# EspSwitchNode.net
KiCad netlist of a schematic drawn in EAGLE
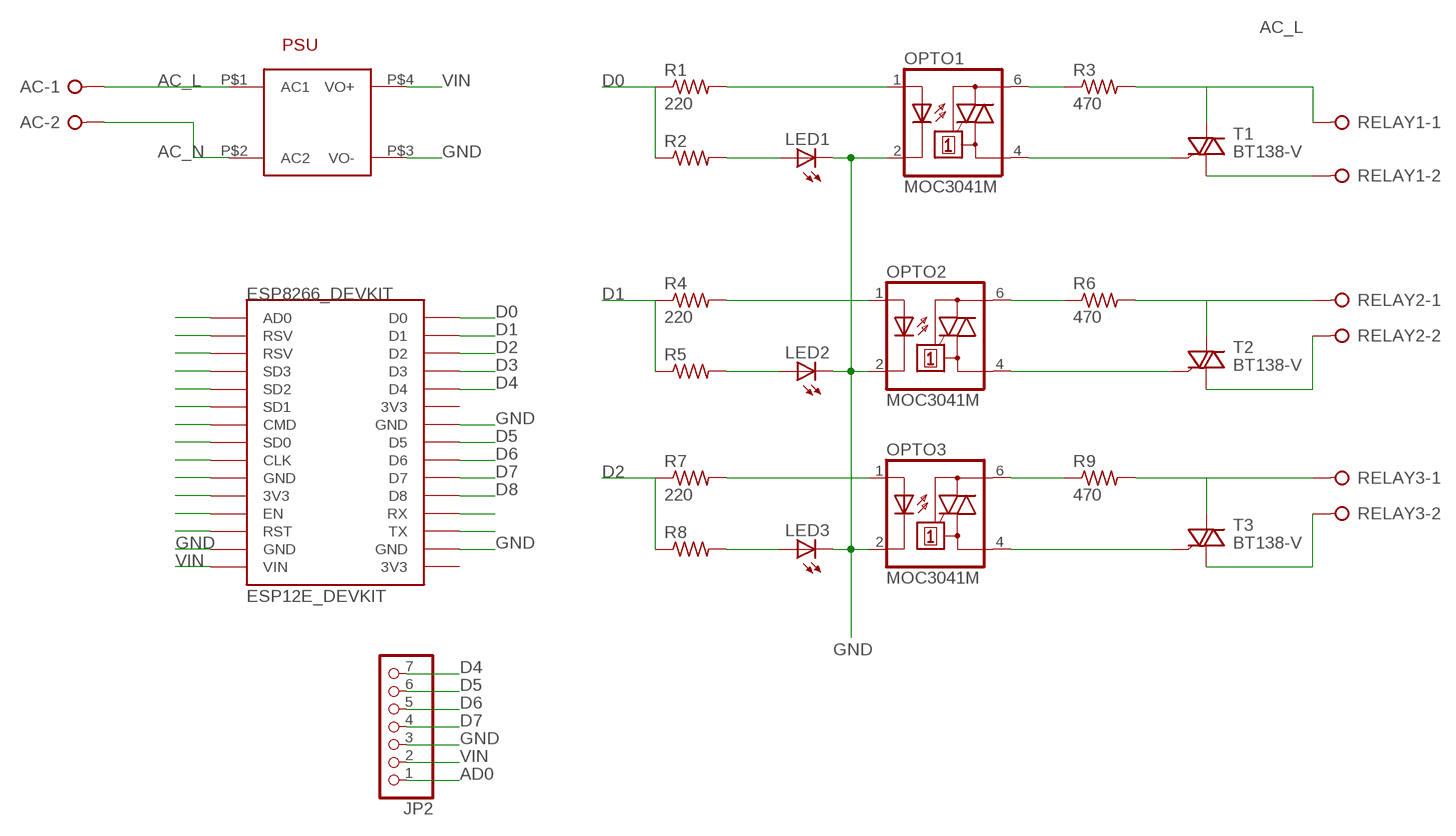
[diagram p0: schematic, sheet 1]

(export (version "E")
  (design (tool "Eeschema 10.0.6"))
  (components
    (comp (ref "AC")
      (value "W237-02P")
      (footprint "eagle-import:W237-132")
      (libsource (lib "eagle-import") (part "W237-02P"))
    )
    (comp (ref "ESP8266_DEVKIT")
      (value "ESP12E_DEVKIT")
      (footprint "eagle-import:ESP12E_DEVKIT")
      (libsource (lib "eagle-import") (part "ESP12E_DEVKIT"))
    )
    (comp (ref "JP2")
      (value "PINHD-1X7")
      (footprint "eagle-import:1X07")
      (libsource (lib "eagle-import") (part "PINHD-1X7"))
    )
    (comp (ref "LED1")
      (value "LEDCHIPLED_0805")
      (footprint "eagle-import:CHIPLED_0805")
      (libsource (lib "eagle-import") (part "LEDCHIPLED_0805"))
    )
    (comp (ref "LED2")
      (value "LEDCHIPLED_0805")
      (footprint "eagle-import:CHIPLED_0805")
      (libsource (lib "eagle-import") (part "LEDCHIPLED_0805"))
    )
    (comp (ref "LED3")
      (value "LEDCHIPLED_0805")
      (footprint "eagle-import:CHIPLED_0805")
      (libsource (lib "eagle-import") (part "LEDCHIPLED_0805"))
    )
    (comp (ref "OPTO1")
      (value "MOC3041M")
      (footprint "eagle-import:DIL06")
      (fields (field (name "MF") "FAIRCHILD SEMICONDUCTOR"))
      (libsource (lib "eagle-import") (part "MOC3041M"))
    )
    (comp (ref "OPTO2")
      (value "MOC3041M")
      (footprint "eagle-import:DIL06")
      (fields (field (name "MF") "FAIRCHILD SEMICONDUCTOR"))
      (libsource (lib "eagle-import") (part "MOC3041M"))
    )
    (comp (ref "OPTO3")
      (value "MOC3041M")
      (footprint "eagle-import:DIL06")
      (fields (field (name "MF") "FAIRCHILD SEMICONDUCTOR"))
      (libsource (lib "eagle-import") (part "MOC3041M"))
    )
    (comp (ref "PSU")
      (value "HLK-PM01")
      (footprint "eagle-import:HLK-PM01")
      (libsource (lib "eagle-import") (part "HLK-PM01"))
    )
    (comp (ref "R1")
      (value "220")
      (footprint "eagle-import:M0805")
      (libsource (lib "eagle-import") (part "R-US_M0805"))
    )
    (comp (ref "R2")
      (value "R-US_M0805")
      (footprint "eagle-import:M0805")
      (libsource (lib "eagle-import") (part "R-US_M0805"))
    )
    (comp (ref "R3")
      (value "470")
      (footprint "eagle-import:M0805")
      (libsource (lib "eagle-import") (part "R-US_M0805"))
    )
    (comp (ref "R4")
      (value "220")
      (footprint "eagle-import:M0805")
      (libsource (lib "eagle-import") (part "R-US_M0805"))
    )
    (comp (ref "R5")
      (value "R-US_M0805")
      (footprint "eagle-import:M0805")
      (libsource (lib "eagle-import") (part "R-US_M0805"))
    )
    (comp (ref "R6")
      (value "470")
      (footprint "eagle-import:M0805")
      (libsource (lib "eagle-import") (part "R-US_M0805"))
    )
    (comp (ref "R7")
      (value "220")
      (footprint "eagle-import:M0805")
      (libsource (lib "eagle-import") (part "R-US_M0805"))
    )
    (comp (ref "R8")
      (value "R-US_M0805")
      (footprint "eagle-import:M0805")
      (libsource (lib "eagle-import") (part "R-US_M0805"))
    )
    (comp (ref "R9")
      (value "470")
      (footprint "eagle-import:M0805")
      (libsource (lib "eagle-import") (part "R-US_M0805"))
    )
    (comp (ref "RELAY1")
      (value "W237-02P")
      (footprint "eagle-import:W237-132")
      (libsource (lib "eagle-import") (part "W237-02P"))
    )
    (comp (ref "RELAY2")
      (value "W237-02P")
      (footprint "eagle-import:W237-132")
      (libsource (lib "eagle-import") (part "W237-02P"))
    )
    (comp (ref "RELAY3")
      (value "W237-02P")
      (footprint "eagle-import:W237-132")
      (libsource (lib "eagle-import") (part "W237-02P"))
    )
    (comp (ref "T1")
      (value "BT138-V")
      (footprint "eagle-import:TO220BV")
      (libsource (lib "eagle-import") (part "BT138-V"))
    )
    (comp (ref "T2")
      (value "BT138-V")
      (footprint "eagle-import:TO220BV")
      (libsource (lib "eagle-import") (part "BT138-V"))
    )
    (comp (ref "T3")
      (value "BT138-V")
      (footprint "eagle-import:TO220BV")
      (libsource (lib "eagle-import") (part "BT138-V"))
    )
  )
  (nets
    (net (code "1") (name "/AC_L") (class "Default")
      (node (ref "AC") (pin "1") (pinfunction "KL_1") (pintype "passive"))
      (node (ref "PSU") (pin "P$1") (pinfunction "AC1_P$1") (pintype "input"))
      (node (ref "R3") (pin "2") (pinfunction "2_2") (pintype "passive"))
      (node (ref "R6") (pin "2") (pinfunction "2_2") (pintype "passive"))
      (node (ref "R9") (pin "2") (pinfunction "2_2") (pintype "passive"))
      (node (ref "RELAY1") (pin "1") (pinfunction "KL_1") (pintype "passive"))
      (node (ref "RELAY2") (pin "1") (pinfunction "KL_1") (pintype "passive"))
      (node (ref "RELAY3") (pin "1") (pinfunction "KL_1") (pintype "passive"))
      (node (ref "T1") (pin "T2") (pinfunction "A2_T2") (pintype "passive"))
      (node (ref "T2") (pin "T2") (pinfunction "A2_T2") (pintype "passive"))
      (node (ref "T3") (pin "T2") (pinfunction "A2_T2") (pintype "passive"))
    )
    (net (code "2") (name "/AC_N") (class "Default")
      (node (ref "AC") (pin "2") (pinfunction "KL_2") (pintype "passive"))
      (node (ref "PSU") (pin "P$2") (pinfunction "AC2_P$2") (pintype "input"))
    )
    (net (code "3") (name "/AD0") (class "Default")
      (node (ref "ESP8266_DEVKIT") (pin "AD0") (pinfunction "AD0_AD0") (pintype "bidirectional"))
      (node (ref "JP2") (pin "1") (pinfunction "1_1") (pintype "passive"))
    )
    (net (code "4") (name "/D0") (class "Default")
      (node (ref "ESP8266_DEVKIT") (pin "D0") (pinfunction "D0_D0") (pintype "bidirectional"))
      (node (ref "R1") (pin "1") (pinfunction "1_1") (pintype "passive"))
      (node (ref "R2") (pin "1") (pinfunction "1_1") (pintype "passive"))
    )
    (net (code "5") (name "/D1") (class "Default")
      (node (ref "ESP8266_DEVKIT") (pin "D1") (pinfunction "D1_D1") (pintype "bidirectional"))
      (node (ref "R4") (pin "1") (pinfunction "1_1") (pintype "passive"))
      (node (ref "R5") (pin "1") (pinfunction "1_1") (pintype "passive"))
    )
    (net (code "6") (name "/D2") (class "Default")
      (node (ref "ESP8266_DEVKIT") (pin "D2") (pinfunction "D2_D2") (pintype "bidirectional"))
      (node (ref "R7") (pin "1") (pinfunction "1_1") (pintype "passive"))
      (node (ref "R8") (pin "1") (pinfunction "1_1") (pintype "passive"))
    )
    (net (code "7") (name "/D3") (class "Default")
      (node (ref "ESP8266_DEVKIT") (pin "D3") (pinfunction "D3_D3") (pintype "bidirectional"))
    )
    (net (code "8") (name "/D4") (class "Default")
      (node (ref "ESP8266_DEVKIT") (pin "D4") (pinfunction "D4_D4") (pintype "bidirectional"))
      (node (ref "JP2") (pin "7") (pinfunction "7_7") (pintype "passive"))
    )
    (net (code "9") (name "/D5") (class "Default")
      (node (ref "ESP8266_DEVKIT") (pin "D5") (pinfunction "D5_D5") (pintype "bidirectional"))
      (node (ref "JP2") (pin "6") (pinfunction "6_6") (pintype "passive"))
    )
    (net (code "10") (name "/D6") (class "Default")
      (node (ref "ESP8266_DEVKIT") (pin "D6") (pinfunction "D6_D6") (pintype "bidirectional"))
      (node (ref "JP2") (pin "5") (pinfunction "5_5") (pintype "passive"))
    )
    (net (code "11") (name "/D7") (class "Default")
      (node (ref "ESP8266_DEVKIT") (pin "D7") (pinfunction "D7_D7") (pintype "bidirectional"))
      (node (ref "JP2") (pin "4") (pinfunction "4_4") (pintype "passive"))
    )
    (net (code "12") (name "/D8") (class "Default")
      (node (ref "ESP8266_DEVKIT") (pin "D8") (pinfunction "D8_D8") (pintype "bidirectional"))
    )
    (net (code "13") (name "/GND") (class "Default")
      (node (ref "ESP8266_DEVKIT") (pin "GND@0") (pinfunction "GND_GND@0") (pintype "bidirectional"))
      (node (ref "ESP8266_DEVKIT") (pin "GND@1") (pinfunction "GND_GND@1") (pintype "bidirectional"))
      (node (ref "ESP8266_DEVKIT") (pin "GND@2") (pinfunction "GND_GND@2") (pintype "bidirectional"))
      (node (ref "ESP8266_DEVKIT") (pin "GND@3") (pinfunction "GND_GND@3") (pintype "bidirectional"))
      (node (ref "JP2") (pin "3") (pinfunction "3_3") (pintype "passive"))
      (node (ref "LED1") (pin "C") (pinfunction "C_C") (pintype "passive"))
      (node (ref "LED2") (pin "C") (pinfunction "C_C") (pintype "passive"))
      (node (ref "LED3") (pin "C") (pinfunction "C_C") (pintype "passive"))
      (node (ref "OPTO1") (pin "2") (pinfunction "C_2") (pintype "passive"))
      (node (ref "OPTO2") (pin "2") (pinfunction "C_2") (pintype "passive"))
      (node (ref "OPTO3") (pin "2") (pinfunction "C_2") (pintype "passive"))
      (node (ref "PSU") (pin "P$3") (pinfunction "VO-_P$3") (pintype "power_in"))
    )
    (net (code "14") (name "/VIN") (class "Default")
      (node (ref "ESP8266_DEVKIT") (pin "VIN") (pinfunction "VIN_VIN") (pintype "bidirectional"))
      (node (ref "JP2") (pin "2") (pinfunction "2_2") (pintype "passive"))
      (node (ref "PSU") (pin "P$4") (pinfunction "VO+_P$4") (pintype "power_in"))
    )
    (net (code "15") (name "Net-(LED1-PadA)") (class "Default")
      (node (ref "LED1") (pin "A") (pinfunction "A_A") (pintype "passive"))
      (node (ref "R2") (pin "2") (pinfunction "2_2") (pintype "passive"))
    )
    (net (code "16") (name "Net-(LED2-PadA)") (class "Default")
      (node (ref "LED2") (pin "A") (pinfunction "A_A") (pintype "passive"))
      (node (ref "R5") (pin "2") (pinfunction "2_2") (pintype "passive"))
    )
    (net (code "17") (name "Net-(LED3-PadA)") (class "Default")
      (node (ref "LED3") (pin "A") (pinfunction "A_A") (pintype "passive"))
      (node (ref "R8") (pin "2") (pinfunction "2_2") (pintype "passive"))
    )
    (net (code "18") (name "Net-(OPTO1-A)") (class "Default")
      (node (ref "OPTO1") (pin "1") (pinfunction "A_1") (pintype "passive"))
      (node (ref "R1") (pin "2") (pinfunction "2_2") (pintype "passive"))
    )
    (net (code "19") (name "Net-(OPTO1-A1)") (class "Default")
      (node (ref "OPTO1") (pin "4") (pinfunction "A1_4") (pintype "passive"))
      (node (ref "T1") (pin "G") (pinfunction "G_G") (pintype "passive"))
    )
    (net (code "20") (name "Net-(OPTO1-A2)") (class "Default")
      (node (ref "OPTO1") (pin "6") (pinfunction "A2_6") (pintype "passive"))
      (node (ref "R3") (pin "1") (pinfunction "1_1") (pintype "passive"))
    )
    (net (code "21") (name "Net-(OPTO2-A)") (class "Default")
      (node (ref "OPTO2") (pin "1") (pinfunction "A_1") (pintype "passive"))
      (node (ref "R4") (pin "2") (pinfunction "2_2") (pintype "passive"))
    )
    (net (code "22") (name "Net-(OPTO2-A1)") (class "Default")
      (node (ref "OPTO2") (pin "4") (pinfunction "A1_4") (pintype "passive"))
      (node (ref "T2") (pin "G") (pinfunction "G_G") (pintype "passive"))
    )
    (net (code "23") (name "Net-(OPTO2-A2)") (class "Default")
      (node (ref "OPTO2") (pin "6") (pinfunction "A2_6") (pintype "passive"))
      (node (ref "R6") (pin "1") (pinfunction "1_1") (pintype "passive"))
    )
    (net (code "24") (name "Net-(OPTO3-A)") (class "Default")
      (node (ref "OPTO3") (pin "1") (pinfunction "A_1") (pintype "passive"))
      (node (ref "R7") (pin "2") (pinfunction "2_2") (pintype "passive"))
    )
    (net (code "25") (name "Net-(OPTO3-A1)") (class "Default")
      (node (ref "OPTO3") (pin "4") (pinfunction "A1_4") (pintype "passive"))
      (node (ref "T3") (pin "G") (pinfunction "G_G") (pintype "passive"))
    )
    (net (code "26") (name "Net-(OPTO3-A2)") (class "Default")
      (node (ref "OPTO3") (pin "6") (pinfunction "A2_6") (pintype "passive"))
      (node (ref "R9") (pin "1") (pinfunction "1_1") (pintype "passive"))
    )
    (net (code "27") (name "Net-(RELAY1B-KL)") (class "Default")
      (node (ref "RELAY1") (pin "2") (pinfunction "KL_2") (pintype "passive"))
      (node (ref "T1") (pin "T1") (pinfunction "A1_T1") (pintype "passive"))
    )
    (net (code "28") (name "Net-(RELAY2B-KL)") (class "Default")
      (node (ref "RELAY2") (pin "2") (pinfunction "KL_2") (pintype "passive"))
      (node (ref "T2") (pin "T1") (pinfunction "A1_T1") (pintype "passive"))
    )
    (net (code "29") (name "Net-(RELAY3B-KL)") (class "Default")
      (node (ref "RELAY3") (pin "2") (pinfunction "KL_2") (pintype "passive"))
      (node (ref "T3") (pin "T1") (pinfunction "A1_T1") (pintype "passive"))
    )
    (net (code "30") (name "unconnected-(ESP8266_DEVKIT-3V3-Pad3V3@0)") (class "Default")
      (node (ref "ESP8266_DEVKIT") (pin "3V3@0") (pinfunction "3V3_3V3@0") (pintype "bidirectional"))
    )
    (net (code "31") (name "unconnected-(ESP8266_DEVKIT-3V3-Pad3V3@1)") (class "Default")
      (node (ref "ESP8266_DEVKIT") (pin "3V3@1") (pinfunction "3V3_3V3@1") (pintype "bidirectional"))
    )
    (net (code "32") (name "unconnected-(ESP8266_DEVKIT-3V3-Pad3V3@2)") (class "Default")
      (node (ref "ESP8266_DEVKIT") (pin "3V3@2") (pinfunction "3V3_3V3@2") (pintype "bidirectional"))
    )
    (net (code "33") (name "unconnected-(ESP8266_DEVKIT-PadCLK)") (class "Default")
      (node (ref "ESP8266_DEVKIT") (pin "CLK") (pinfunction "CLK_CLK") (pintype "bidirectional"))
    )
    (net (code "34") (name "unconnected-(ESP8266_DEVKIT-PadCMD)") (class "Default")
      (node (ref "ESP8266_DEVKIT") (pin "CMD") (pinfunction "CMD_CMD") (pintype "bidirectional"))
    )
    (net (code "35") (name "unconnected-(ESP8266_DEVKIT-PadEN)") (class "Default")
      (node (ref "ESP8266_DEVKIT") (pin "EN") (pinfunction "EN_EN") (pintype "bidirectional"))
    )
    (net (code "36") (name "unconnected-(ESP8266_DEVKIT-PadRST)") (class "Default")
      (node (ref "ESP8266_DEVKIT") (pin "RST") (pinfunction "RST_RST") (pintype "bidirectional"))
    )
    (net (code "37") (name "unconnected-(ESP8266_DEVKIT-PadRX)") (class "Default")
      (node (ref "ESP8266_DEVKIT") (pin "RX") (pinfunction "RX_RX") (pintype "bidirectional"))
    )
    (net (code "38") (name "unconnected-(ESP8266_DEVKIT-PadSD0)") (class "Default")
      (node (ref "ESP8266_DEVKIT") (pin "SD0") (pinfunction "SD0_SD0") (pintype "bidirectional"))
    )
    (net (code "39") (name "unconnected-(ESP8266_DEVKIT-PadSD1)") (class "Default")
      (node (ref "ESP8266_DEVKIT") (pin "SD1") (pinfunction "SD1_SD1") (pintype "bidirectional"))
    )
    (net (code "40") (name "unconnected-(ESP8266_DEVKIT-PadSD2)") (class "Default")
      (node (ref "ESP8266_DEVKIT") (pin "SD2") (pinfunction "SD2_SD2") (pintype "bidirectional"))
    )
    (net (code "41") (name "unconnected-(ESP8266_DEVKIT-PadSD3)") (class "Default")
      (node (ref "ESP8266_DEVKIT") (pin "SD3") (pinfunction "SD3_SD3") (pintype "bidirectional"))
    )
    (net (code "42") (name "unconnected-(ESP8266_DEVKIT-PadTX)") (class "Default")
      (node (ref "ESP8266_DEVKIT") (pin "TX") (pinfunction "TX_TX") (pintype "bidirectional"))
    )
    (net (code "43") (name "unconnected-(ESP8266_DEVKIT-RSV-PadRSV@0)") (class "Default")
      (node (ref "ESP8266_DEVKIT") (pin "RSV@0") (pinfunction "RSV_RSV@0") (pintype "bidirectional"))
    )
    (net (code "44") (name "unconnected-(ESP8266_DEVKIT-RSV-PadRSV@1)") (class "Default")
      (node (ref "ESP8266_DEVKIT") (pin "RSV@1") (pinfunction "RSV_RSV@1") (pintype "bidirectional"))
    )
  )
)
